# DHQ11.net
KiCad netlist of a schematic drawn in Altium Designer
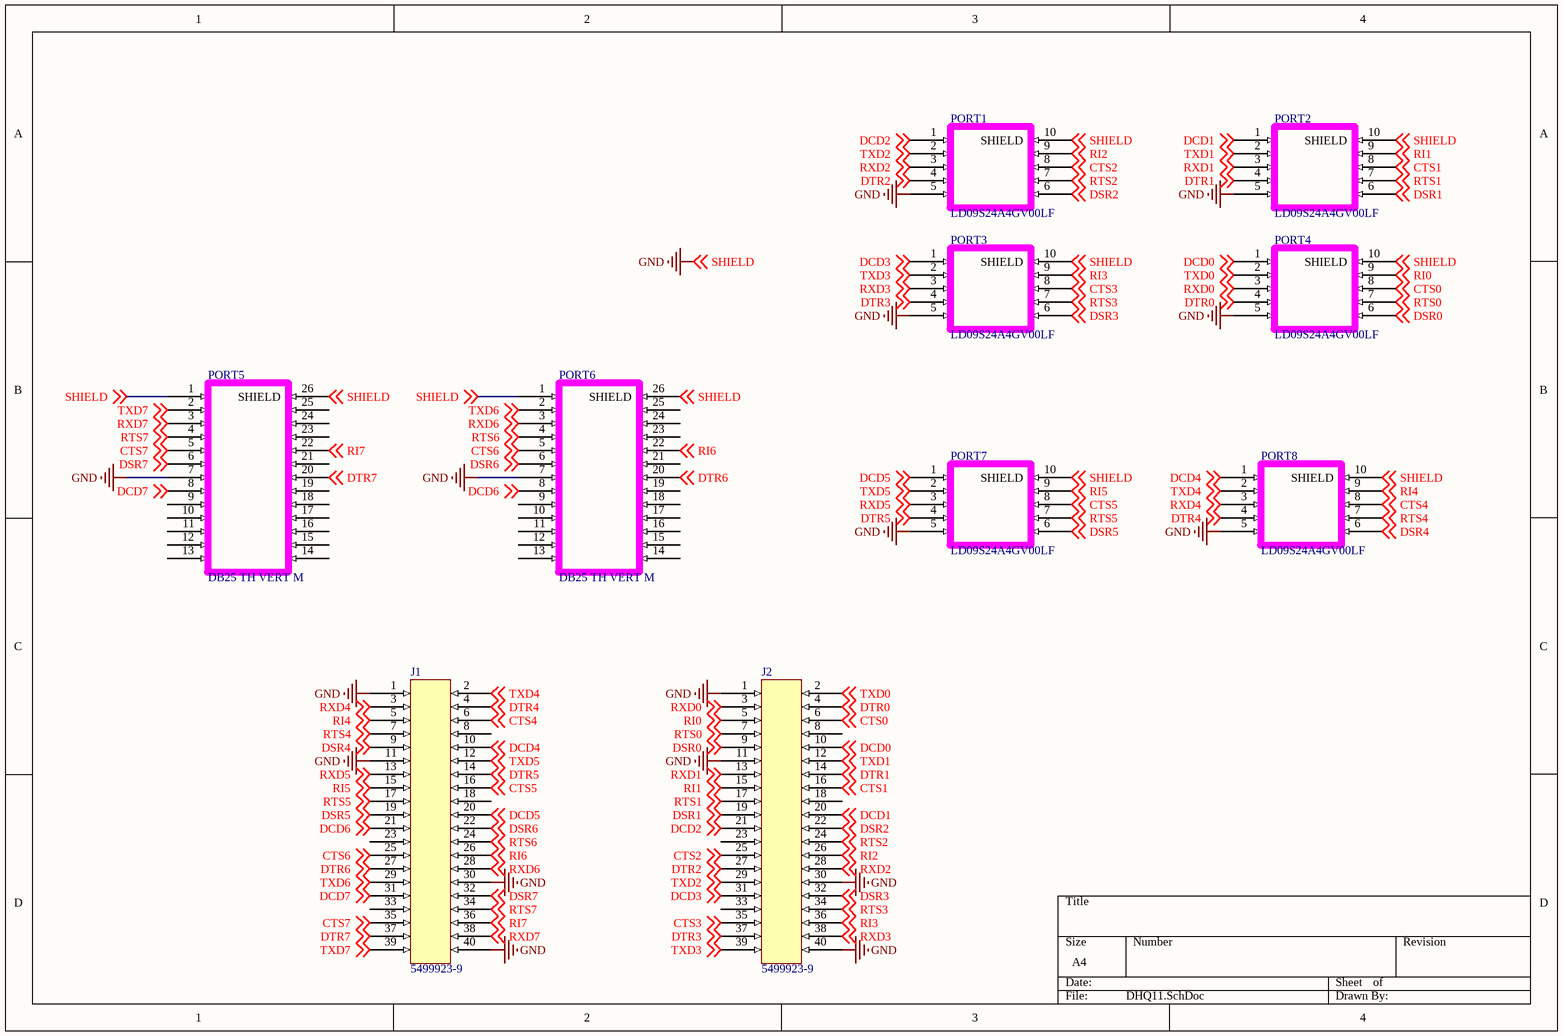
[diagram p0: DHQ11.SchDoc]

(export (version "E")
  (design (tool "Eeschema 10.0.6"))
  (components
    (comp (ref "J1")
      (value "5499923-9")
      (footprint "HDR2X20 Ejector")
      (description "2X20 Latch VERT HDR M TH")
      (libsource (lib "Kanitti") (part "5499923-9"))
    )
    (comp (ref "J2")
      (value "5499923-9")
      (footprint "HDR2X20 Ejector")
      (description "2X20 Latch VERT HDR M TH")
      (libsource (lib "Kanitti") (part "5499923-9"))
    )
    (comp (ref "PORT1")
      (value "LD09S24A4GV00LF")
      (footprint "LD09S24A4GV00LF")
      (libsource (lib "Kanitti") (part "DB9 VERT TH M"))
    )
    (comp (ref "PORT2")
      (value "LD09S24A4GV00LF")
      (footprint "LD09S24A4GV00LF")
      (libsource (lib "Kanitti") (part "DB9 VERT TH M"))
    )
    (comp (ref "PORT3")
      (value "LD09S24A4GV00LF")
      (footprint "LD09S24A4GV00LF")
      (libsource (lib "Kanitti") (part "DB9 VERT TH M"))
    )
    (comp (ref "PORT4")
      (value "LD09S24A4GV00LF")
      (footprint "LD09S24A4GV00LF")
      (libsource (lib "Kanitti") (part "DB9 VERT TH M"))
    )
    (comp (ref "PORT5")
      (value "DB25 TH VERT M")
      (footprint "KANITTI:D25P24A6GV00LF")
      (libsource (lib "Kanitti") (part "DB25 TH VERT M"))
    )
    (comp (ref "PORT6")
      (value "DB25 TH VERT M")
      (footprint "KANITTI:D25P24A6GV00LF")
      (libsource (lib "Kanitti") (part "DB25 TH VERT M"))
    )
    (comp (ref "PORT7")
      (value "LD09S24A4GV00LF")
      (footprint "LD09S24A4GV00LF")
      (libsource (lib "Kanitti") (part "DB9 VERT TH M"))
    )
    (comp (ref "PORT8")
      (value "LD09S24A4GV00LF")
      (footprint "LD09S24A4GV00LF")
      (libsource (lib "Kanitti") (part "DB9 VERT TH M"))
    )
  )
  (nets
    (net (code "1") (name "CTS0") (class "Default")
      (node (ref "J2") (pin "6") (pintype "input"))
      (node (ref "PORT4") (pin "8") (pintype "input"))
    )
    (net (code "2") (name "CTS1") (class "Default")
      (node (ref "J2") (pin "16") (pintype "input"))
      (node (ref "PORT2") (pin "8") (pintype "input"))
    )
    (net (code "3") (name "CTS2") (class "Default")
      (node (ref "J2") (pin "25") (pintype "input"))
      (node (ref "PORT1") (pin "8") (pintype "input"))
    )
    (net (code "4") (name "CTS3") (class "Default")
      (node (ref "J2") (pin "35") (pintype "input"))
      (node (ref "PORT3") (pin "8") (pintype "input"))
    )
    (net (code "5") (name "CTS4") (class "Default")
      (node (ref "J1") (pin "6") (pintype "input"))
      (node (ref "PORT8") (pin "8") (pintype "input"))
    )
    (net (code "6") (name "CTS5") (class "Default")
      (node (ref "J1") (pin "16") (pintype "input"))
      (node (ref "PORT7") (pin "8") (pintype "input"))
    )
    (net (code "7") (name "CTS6") (class "Default")
      (node (ref "J1") (pin "25") (pintype "input"))
      (node (ref "PORT6") (pin "5") (pintype "input"))
    )
    (net (code "8") (name "CTS7") (class "Default")
      (node (ref "J1") (pin "35") (pintype "input"))
      (node (ref "PORT5") (pin "5") (pintype "input"))
    )
    (net (code "9") (name "DCD0") (class "Default")
      (node (ref "J2") (pin "10") (pintype "input"))
      (node (ref "PORT4") (pin "1") (pintype "input"))
    )
    (net (code "10") (name "DCD1") (class "Default")
      (node (ref "J2") (pin "20") (pintype "input"))
      (node (ref "PORT2") (pin "1") (pintype "input"))
    )
    (net (code "11") (name "DCD2") (class "Default")
      (node (ref "J2") (pin "21") (pintype "input"))
      (node (ref "PORT1") (pin "1") (pintype "input"))
    )
    (net (code "12") (name "DCD3") (class "Default")
      (node (ref "J2") (pin "31") (pintype "input"))
      (node (ref "PORT3") (pin "1") (pintype "input"))
    )
    (net (code "13") (name "DCD4") (class "Default")
      (node (ref "J1") (pin "10") (pintype "input"))
      (node (ref "PORT8") (pin "1") (pintype "input"))
    )
    (net (code "14") (name "DCD5") (class "Default")
      (node (ref "J1") (pin "20") (pintype "input"))
      (node (ref "PORT7") (pin "1") (pintype "input"))
    )
    (net (code "15") (name "DCD6") (class "Default")
      (node (ref "J1") (pin "21") (pintype "input"))
      (node (ref "PORT6") (pin "8") (pintype "input"))
    )
    (net (code "16") (name "DCD7") (class "Default")
      (node (ref "J1") (pin "31") (pintype "input"))
      (node (ref "PORT5") (pin "8") (pintype "input"))
    )
    (net (code "17") (name "DSR0") (class "Default")
      (node (ref "J2") (pin "9") (pintype "input"))
      (node (ref "PORT4") (pin "6") (pintype "input"))
    )
    (net (code "18") (name "DSR1") (class "Default")
      (node (ref "J2") (pin "19") (pintype "input"))
      (node (ref "PORT2") (pin "6") (pintype "input"))
    )
    (net (code "19") (name "DSR2") (class "Default")
      (node (ref "J2") (pin "22") (pintype "input"))
      (node (ref "PORT1") (pin "6") (pintype "input"))
    )
    (net (code "20") (name "DSR3") (class "Default")
      (node (ref "J2") (pin "32") (pintype "input"))
      (node (ref "PORT3") (pin "6") (pintype "input"))
    )
    (net (code "21") (name "DSR4") (class "Default")
      (node (ref "J1") (pin "9") (pintype "input"))
      (node (ref "PORT8") (pin "6") (pintype "input"))
    )
    (net (code "22") (name "DSR5") (class "Default")
      (node (ref "J1") (pin "19") (pintype "input"))
      (node (ref "PORT7") (pin "6") (pintype "input"))
    )
    (net (code "23") (name "DSR6") (class "Default")
      (node (ref "J1") (pin "22") (pintype "input"))
      (node (ref "PORT6") (pin "6") (pintype "input"))
    )
    (net (code "24") (name "DSR7") (class "Default")
      (node (ref "J1") (pin "32") (pintype "input"))
      (node (ref "PORT5") (pin "6") (pintype "input"))
    )
    (net (code "25") (name "DTR0") (class "Default")
      (node (ref "J2") (pin "4") (pintype "input"))
      (node (ref "PORT4") (pin "4") (pintype "input"))
    )
    (net (code "26") (name "DTR1") (class "Default")
      (node (ref "J2") (pin "14") (pintype "input"))
      (node (ref "PORT2") (pin "4") (pintype "input"))
    )
    (net (code "27") (name "DTR2") (class "Default")
      (node (ref "J2") (pin "27") (pintype "input"))
      (node (ref "PORT1") (pin "4") (pintype "input"))
    )
    (net (code "28") (name "DTR3") (class "Default")
      (node (ref "J2") (pin "37") (pintype "input"))
      (node (ref "PORT3") (pin "4") (pintype "input"))
    )
    (net (code "29") (name "DTR4") (class "Default")
      (node (ref "J1") (pin "4") (pintype "input"))
      (node (ref "PORT8") (pin "4") (pintype "input"))
    )
    (net (code "30") (name "DTR5") (class "Default")
      (node (ref "J1") (pin "14") (pintype "input"))
      (node (ref "PORT7") (pin "4") (pintype "input"))
    )
    (net (code "31") (name "DTR6") (class "Default")
      (node (ref "J1") (pin "27") (pintype "input"))
      (node (ref "PORT6") (pin "20") (pintype "input"))
    )
    (net (code "32") (name "DTR7") (class "Default")
      (node (ref "J1") (pin "37") (pintype "input"))
      (node (ref "PORT5") (pin "20") (pintype "input"))
    )
    (net (code "33") (name "GND") (class "Default")
      (node (ref "J1") (pin "1") (pintype "input"))
      (node (ref "J1") (pin "11") (pintype "input"))
      (node (ref "J1") (pin "30") (pintype "input"))
      (node (ref "J1") (pin "40") (pintype "input"))
      (node (ref "J2") (pin "1") (pintype "input"))
      (node (ref "J2") (pin "11") (pintype "input"))
      (node (ref "J2") (pin "30") (pintype "input"))
      (node (ref "J2") (pin "40") (pintype "input"))
      (node (ref "PORT1") (pin "10") (pinfunction "SHIELD_10") (pintype "input"))
      (node (ref "PORT1") (pin "5") (pintype "input"))
      (node (ref "PORT2") (pin "10") (pinfunction "SHIELD_10") (pintype "input"))
      (node (ref "PORT2") (pin "5") (pintype "input"))
      (node (ref "PORT3") (pin "10") (pinfunction "SHIELD_10") (pintype "input"))
      (node (ref "PORT3") (pin "5") (pintype "input"))
      (node (ref "PORT4") (pin "10") (pinfunction "SHIELD_10") (pintype "input"))
      (node (ref "PORT4") (pin "5") (pintype "input"))
      (node (ref "PORT5") (pin "1") (pintype "input"))
      (node (ref "PORT5") (pin "26") (pinfunction "SHIELD_26") (pintype "input"))
      (node (ref "PORT5") (pin "7") (pintype "input"))
      (node (ref "PORT6") (pin "1") (pintype "input"))
      (node (ref "PORT6") (pin "26") (pinfunction "SHIELD_26") (pintype "input"))
      (node (ref "PORT6") (pin "7") (pintype "input"))
      (node (ref "PORT7") (pin "10") (pinfunction "SHIELD_10") (pintype "input"))
      (node (ref "PORT7") (pin "5") (pintype "input"))
      (node (ref "PORT8") (pin "10") (pinfunction "SHIELD_10") (pintype "input"))
      (node (ref "PORT8") (pin "5") (pintype "input"))
    )
    (net (code "34") (name "RI0") (class "Default")
      (node (ref "J2") (pin "5") (pintype "input"))
      (node (ref "PORT4") (pin "9") (pintype "input"))
    )
    (net (code "35") (name "RI1") (class "Default")
      (node (ref "J2") (pin "15") (pintype "input"))
      (node (ref "PORT2") (pin "9") (pintype "input"))
    )
    (net (code "36") (name "RI2") (class "Default")
      (node (ref "J2") (pin "26") (pintype "input"))
      (node (ref "PORT1") (pin "9") (pintype "input"))
    )
    (net (code "37") (name "RI3") (class "Default")
      (node (ref "J2") (pin "36") (pintype "input"))
      (node (ref "PORT3") (pin "9") (pintype "input"))
    )
    (net (code "38") (name "RI4") (class "Default")
      (node (ref "J1") (pin "5") (pintype "input"))
      (node (ref "PORT8") (pin "9") (pintype "input"))
    )
    (net (code "39") (name "RI5") (class "Default")
      (node (ref "J1") (pin "15") (pintype "input"))
      (node (ref "PORT7") (pin "9") (pintype "input"))
    )
    (net (code "40") (name "RI6") (class "Default")
      (node (ref "J1") (pin "26") (pintype "input"))
      (node (ref "PORT6") (pin "22") (pintype "input"))
    )
    (net (code "41") (name "RI7") (class "Default")
      (node (ref "J1") (pin "36") (pintype "input"))
      (node (ref "PORT5") (pin "22") (pintype "input"))
    )
    (net (code "42") (name "RTS0") (class "Default")
      (node (ref "J2") (pin "7") (pintype "input"))
      (node (ref "PORT4") (pin "7") (pintype "input"))
    )
    (net (code "43") (name "RTS1") (class "Default")
      (node (ref "J2") (pin "17") (pintype "input"))
      (node (ref "PORT2") (pin "7") (pintype "input"))
    )
    (net (code "44") (name "RTS2") (class "Default")
      (node (ref "J2") (pin "24") (pintype "input"))
      (node (ref "PORT1") (pin "7") (pintype "input"))
    )
    (net (code "45") (name "RTS3") (class "Default")
      (node (ref "J2") (pin "34") (pintype "input"))
      (node (ref "PORT3") (pin "7") (pintype "input"))
    )
    (net (code "46") (name "RTS4") (class "Default")
      (node (ref "J1") (pin "7") (pintype "input"))
      (node (ref "PORT8") (pin "7") (pintype "input"))
    )
    (net (code "47") (name "RTS5") (class "Default")
      (node (ref "J1") (pin "17") (pintype "input"))
      (node (ref "PORT7") (pin "7") (pintype "input"))
    )
    (net (code "48") (name "RTS6") (class "Default")
      (node (ref "J1") (pin "24") (pintype "input"))
      (node (ref "PORT6") (pin "4") (pintype "input"))
    )
    (net (code "49") (name "RTS7") (class "Default")
      (node (ref "J1") (pin "34") (pintype "input"))
      (node (ref "PORT5") (pin "4") (pintype "input"))
    )
    (net (code "50") (name "RXD0") (class "Default")
      (node (ref "J2") (pin "3") (pintype "input"))
      (node (ref "PORT4") (pin "3") (pintype "input"))
    )
    (net (code "51") (name "RXD1") (class "Default")
      (node (ref "J2") (pin "13") (pintype "input"))
      (node (ref "PORT2") (pin "3") (pintype "input"))
    )
    (net (code "52") (name "RXD2") (class "Default")
      (node (ref "J2") (pin "28") (pintype "input"))
      (node (ref "PORT1") (pin "3") (pintype "input"))
    )
    (net (code "53") (name "RXD3") (class "Default")
      (node (ref "J2") (pin "38") (pintype "input"))
      (node (ref "PORT3") (pin "3") (pintype "input"))
    )
    (net (code "54") (name "RXD4") (class "Default")
      (node (ref "J1") (pin "3") (pintype "input"))
      (node (ref "PORT8") (pin "3") (pintype "input"))
    )
    (net (code "55") (name "RXD5") (class "Default")
      (node (ref "J1") (pin "13") (pintype "input"))
      (node (ref "PORT7") (pin "3") (pintype "input"))
    )
    (net (code "56") (name "RXD6") (class "Default")
      (node (ref "J1") (pin "28") (pintype "input"))
      (node (ref "PORT6") (pin "3") (pintype "input"))
    )
    (net (code "57") (name "RXD7") (class "Default")
      (node (ref "J1") (pin "38") (pintype "input"))
      (node (ref "PORT5") (pin "3") (pintype "input"))
    )
    (net (code "58") (name "TXD0") (class "Default")
      (node (ref "J2") (pin "2") (pintype "input"))
      (node (ref "PORT4") (pin "2") (pintype "input"))
    )
    (net (code "59") (name "TXD1") (class "Default")
      (node (ref "J2") (pin "12") (pintype "input"))
      (node (ref "PORT2") (pin "2") (pintype "input"))
    )
    (net (code "60") (name "TXD2") (class "Default")
      (node (ref "J2") (pin "29") (pintype "input"))
      (node (ref "PORT1") (pin "2") (pintype "input"))
    )
    (net (code "61") (name "TXD3") (class "Default")
      (node (ref "J2") (pin "39") (pintype "input"))
      (node (ref "PORT3") (pin "2") (pintype "input"))
    )
    (net (code "62") (name "TXD4") (class "Default")
      (node (ref "J1") (pin "2") (pintype "input"))
      (node (ref "PORT8") (pin "2") (pintype "input"))
    )
    (net (code "63") (name "TXD5") (class "Default")
      (node (ref "J1") (pin "12") (pintype "input"))
      (node (ref "PORT7") (pin "2") (pintype "input"))
    )
    (net (code "64") (name "TXD6") (class "Default")
      (node (ref "J1") (pin "29") (pintype "input"))
      (node (ref "PORT6") (pin "2") (pintype "input"))
    )
    (net (code "65") (name "TXD7") (class "Default")
      (node (ref "J1") (pin "39") (pintype "input"))
      (node (ref "PORT5") (pin "2") (pintype "input"))
    )
    (net (code "66") (name "unconnected-(J1-Pad8)") (class "Default")
      (node (ref "J1") (pin "8") (pintype "input"))
    )
    (net (code "67") (name "unconnected-(J1-Pad18)") (class "Default")
      (node (ref "J1") (pin "18") (pintype "input"))
    )
    (net (code "68") (name "unconnected-(J1-Pad23)") (class "Default")
      (node (ref "J1") (pin "23") (pintype "input"))
    )
    (net (code "69") (name "unconnected-(J1-Pad33)") (class "Default")
      (node (ref "J1") (pin "33") (pintype "input"))
    )
    (net (code "70") (name "unconnected-(J2-Pad8)") (class "Default")
      (node (ref "J2") (pin "8") (pintype "input"))
    )
    (net (code "71") (name "unconnected-(J2-Pad18)") (class "Default")
      (node (ref "J2") (pin "18") (pintype "input"))
    )
    (net (code "72") (name "unconnected-(J2-Pad23)") (class "Default")
      (node (ref "J2") (pin "23") (pintype "input"))
    )
    (net (code "73") (name "unconnected-(J2-Pad33)") (class "Default")
      (node (ref "J2") (pin "33") (pintype "input"))
    )
    (net (code "74") (name "unconnected-(PORT5-Pad9)") (class "Default")
      (node (ref "PORT5") (pin "9") (pintype "input"))
    )
    (net (code "75") (name "unconnected-(PORT5-Pad10)") (class "Default")
      (node (ref "PORT5") (pin "10") (pintype "input"))
    )
    (net (code "76") (name "unconnected-(PORT5-Pad11)") (class "Default")
      (node (ref "PORT5") (pin "11") (pintype "input"))
    )
    (net (code "77") (name "unconnected-(PORT5-Pad12)") (class "Default")
      (node (ref "PORT5") (pin "12") (pintype "input"))
    )
    (net (code "78") (name "unconnected-(PORT5-Pad13)") (class "Default")
      (node (ref "PORT5") (pin "13") (pintype "input"))
    )
    (net (code "79") (name "unconnected-(PORT5-Pad14)") (class "Default")
      (node (ref "PORT5") (pin "14") (pintype "input"))
    )
    (net (code "80") (name "unconnected-(PORT5-Pad15)") (class "Default")
      (node (ref "PORT5") (pin "15") (pintype "input"))
    )
    (net (code "81") (name "unconnected-(PORT5-Pad16)") (class "Default")
      (node (ref "PORT5") (pin "16") (pintype "input"))
    )
    (net (code "82") (name "unconnected-(PORT5-Pad17)") (class "Default")
      (node (ref "PORT5") (pin "17") (pintype "input"))
    )
    (net (code "83") (name "unconnected-(PORT5-Pad18)") (class "Default")
      (node (ref "PORT5") (pin "18") (pintype "input"))
    )
    (net (code "84") (name "unconnected-(PORT5-Pad19)") (class "Default")
      (node (ref "PORT5") (pin "19") (pintype "input"))
    )
    (net (code "85") (name "unconnected-(PORT5-Pad21)") (class "Default")
      (node (ref "PORT5") (pin "21") (pintype "input"))
    )
    (net (code "86") (name "unconnected-(PORT5-Pad23)") (class "Default")
      (node (ref "PORT5") (pin "23") (pintype "input"))
    )
    (net (code "87") (name "unconnected-(PORT5-Pad24)") (class "Default")
      (node (ref "PORT5") (pin "24") (pintype "input"))
    )
    (net (code "88") (name "unconnected-(PORT5-Pad25)") (class "Default")
      (node (ref "PORT5") (pin "25") (pintype "input"))
    )
    (net (code "89") (name "unconnected-(PORT6-Pad9)") (class "Default")
      (node (ref "PORT6") (pin "9") (pintype "input"))
    )
    (net (code "90") (name "unconnected-(PORT6-Pad10)") (class "Default")
      (node (ref "PORT6") (pin "10") (pintype "input"))
    )
    (net (code "91") (name "unconnected-(PORT6-Pad11)") (class "Default")
      (node (ref "PORT6") (pin "11") (pintype "input"))
    )
    (net (code "92") (name "unconnected-(PORT6-Pad12)") (class "Default")
      (node (ref "PORT6") (pin "12") (pintype "input"))
    )
    (net (code "93") (name "unconnected-(PORT6-Pad13)") (class "Default")
      (node (ref "PORT6") (pin "13") (pintype "input"))
    )
    (net (code "94") (name "unconnected-(PORT6-Pad14)") (class "Default")
      (node (ref "PORT6") (pin "14") (pintype "input"))
    )
    (net (code "95") (name "unconnected-(PORT6-Pad15)") (class "Default")
      (node (ref "PORT6") (pin "15") (pintype "input"))
    )
    (net (code "96") (name "unconnected-(PORT6-Pad16)") (class "Default")
      (node (ref "PORT6") (pin "16") (pintype "input"))
    )
    (net (code "97") (name "unconnected-(PORT6-Pad17)") (class "Default")
      (node (ref "PORT6") (pin "17") (pintype "input"))
    )
    (net (code "98") (name "unconnected-(PORT6-Pad18)") (class "Default")
      (node (ref "PORT6") (pin "18") (pintype "input"))
    )
    (net (code "99") (name "unconnected-(PORT6-Pad19)") (class "Default")
      (node (ref "PORT6") (pin "19") (pintype "input"))
    )
    (net (code "100") (name "unconnected-(PORT6-Pad21)") (class "Default")
      (node (ref "PORT6") (pin "21") (pintype "input"))
    )
    (net (code "101") (name "unconnected-(PORT6-Pad23)") (class "Default")
      (node (ref "PORT6") (pin "23") (pintype "input"))
    )
    (net (code "102") (name "unconnected-(PORT6-Pad24)") (class "Default")
      (node (ref "PORT6") (pin "24") (pintype "input"))
    )
    (net (code "103") (name "unconnected-(PORT6-Pad25)") (class "Default")
      (node (ref "PORT6") (pin "25") (pintype "input"))
    )
  )
)
